# swt-001.net
KiCad netlist of a schematic drawn in EAGLE
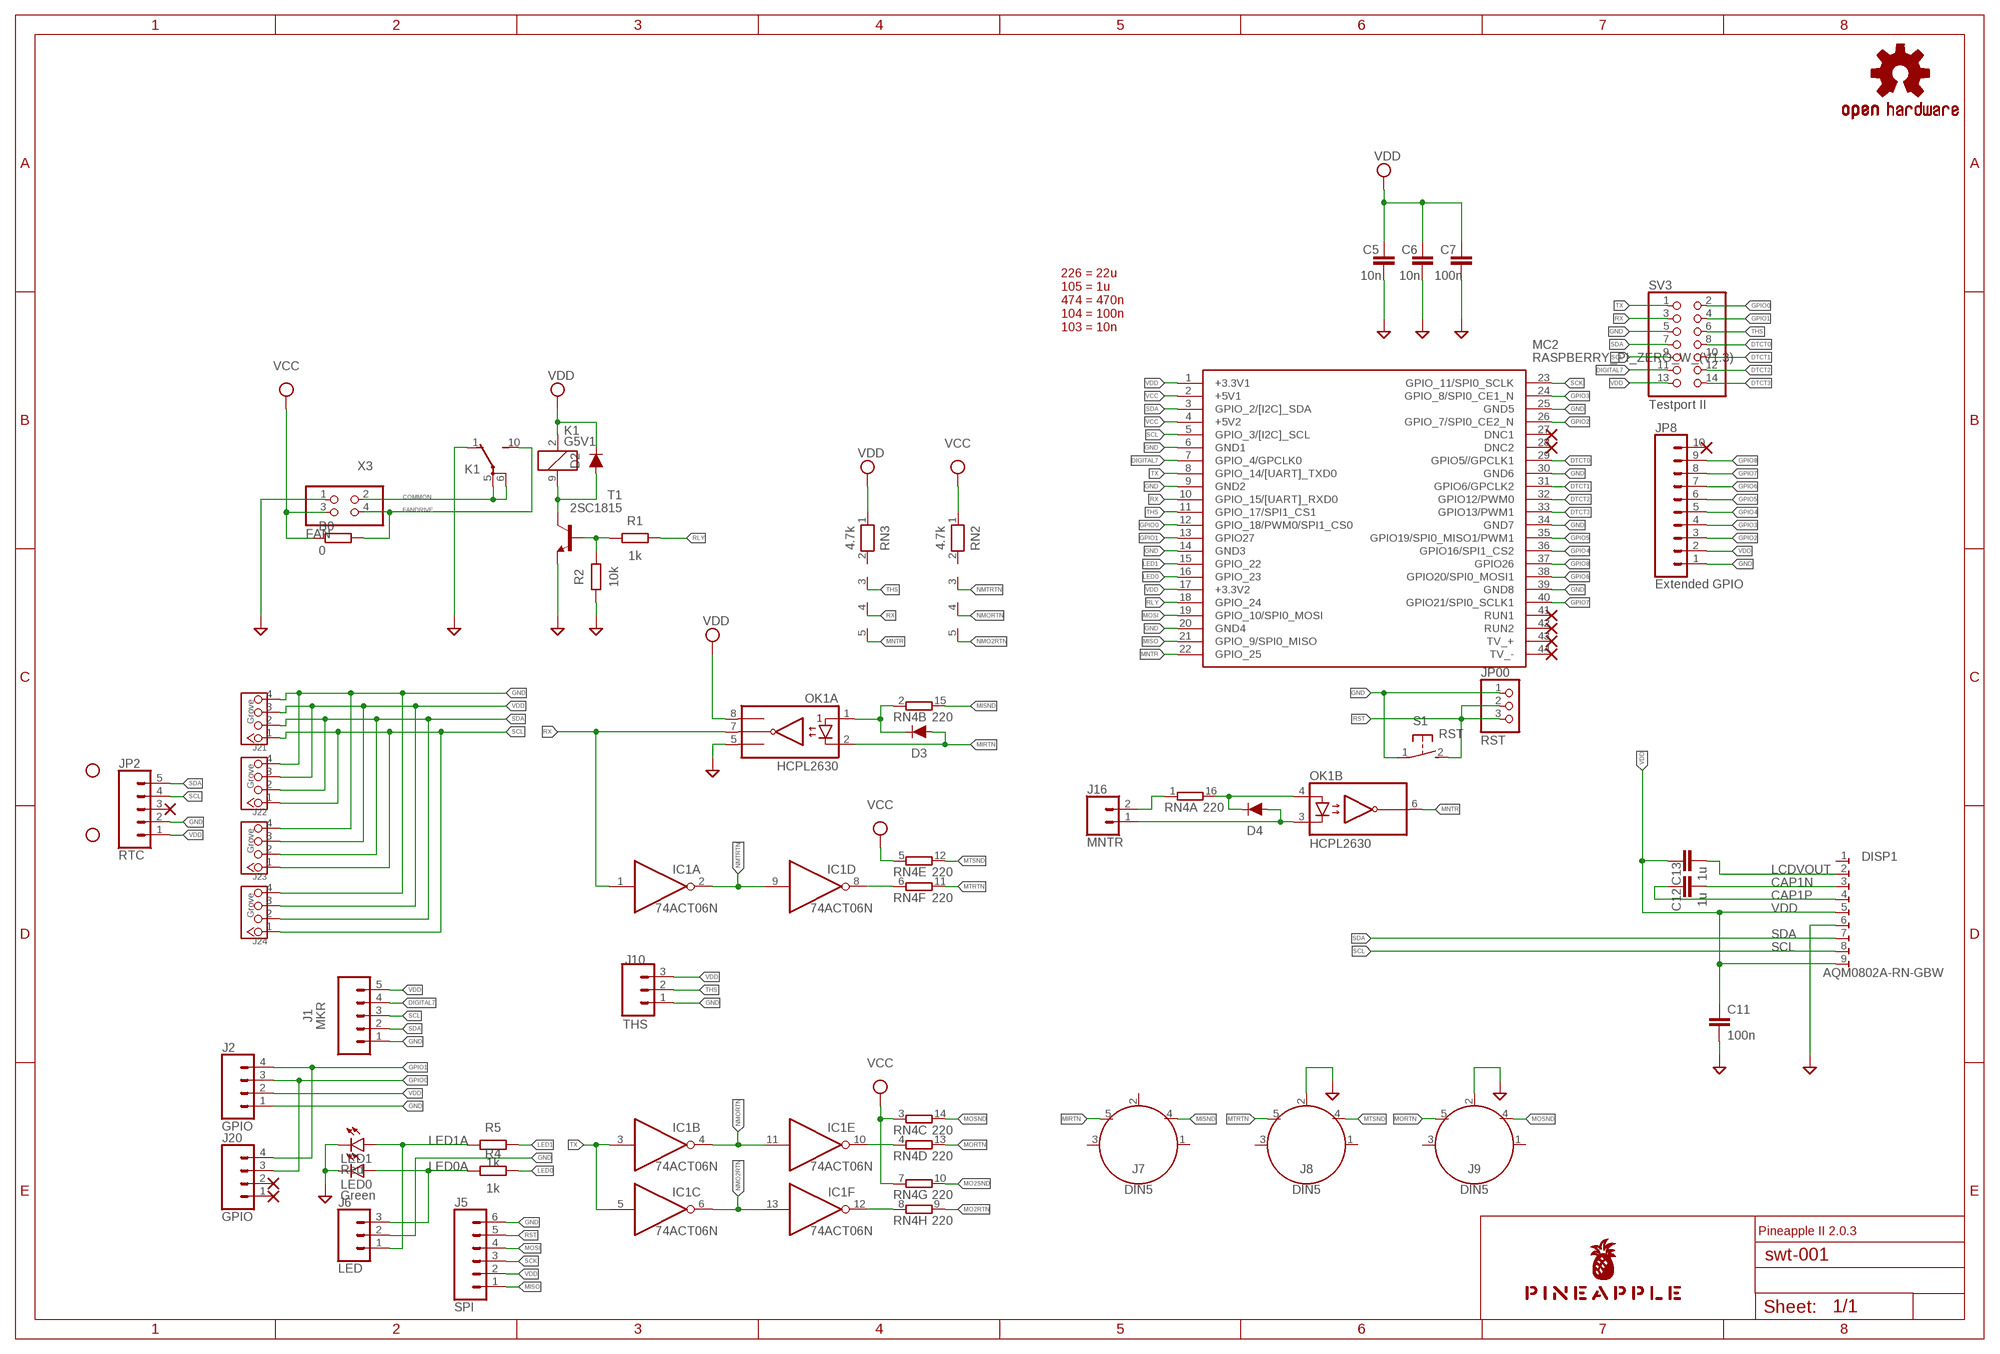
[diagram p0: schematic, sheet 1]

(export (version "E")
  (design (tool "Eeschema 10.0.6"))
  (components
    (comp (ref "B0")
      (value "0")
      (footprint "eagle-import:M3216")
      (libsource (lib "eagle-import") (part "R-EU_M3216"))
    )
    (comp (ref "C5")
      (value "10n")
      (footprint "eagle-import:C025-024X044")
      (libsource (lib "eagle-import") (part "resistor_348_C-EU025-024X044"))
    )
    (comp (ref "C6")
      (value "10n")
      (footprint "eagle-import:C025-024X044")
      (libsource (lib "eagle-import") (part "resistor_348_C-EU025-024X044"))
    )
    (comp (ref "C7")
      (value "100n")
      (footprint "eagle-import:C025-024X044")
      (libsource (lib "eagle-import") (part "resistor_348_C-EU025-024X044"))
    )
    (comp (ref "C11")
      (value "100n")
      (footprint "eagle-import:C025-024X044")
      (libsource (lib "eagle-import") (part "C-EU025-024X044"))
    )
    (comp (ref "C12")
      (value "1u")
      (footprint "eagle-import:C050-024X044")
      (libsource (lib "eagle-import") (part "C-EU050-024X044"))
    )
    (comp (ref "C13")
      (value "1u")
      (footprint "eagle-import:C050-024X044")
      (libsource (lib "eagle-import") (part "C-EU050-024X044"))
    )
    (comp (ref "D2")
      (value "DIODE-1N4148")
      (footprint "eagle-import:DIODE-1N4148")
      (libsource (lib "eagle-import") (part "DIODE-1N4148"))
    )
    (comp (ref "D3")
      (value "DIODE-1N4148")
      (footprint "eagle-import:DIODE-1N4148")
      (libsource (lib "eagle-import") (part "DIODE-1N4148"))
    )
    (comp (ref "D4")
      (value "DIODE-1N4148")
      (footprint "eagle-import:DIODE-1N4148")
      (libsource (lib "eagle-import") (part "DIODE-1N4148"))
    )
    (comp (ref "DISP1")
      (value "AQM0802A-RN-GBW")
      (footprint "eagle-import:AQM0802A-RN-GBW-FOOTPRINT")
      (libsource (lib "eagle-import") (part "AQM0802A-RN-GBW"))
    )
    (comp (ref "H1")
      (value "STAND-OFF")
      (footprint "eagle-import:STAND-OFF")
      (libsource (lib "eagle-import") (part "STAND-OFF"))
    )
    (comp (ref "H2")
      (value "STAND-OFF")
      (footprint "eagle-import:STAND-OFF")
      (libsource (lib "eagle-import") (part "STAND-OFF"))
    )
    (comp (ref "IC1")
      (value "74ACT06N")
      (footprint "eagle-import:DIL14")
      (libsource (lib "eagle-import") (part "7406NACT"))
    )
    (comp (ref "J1")
      (value "MKR")
      (footprint "eagle-import:JST-5-PTH")
      (libsource (lib "eagle-import") (part "CONN_05JST"))
    )
    (comp (ref "J2")
      (value "GPIO")
      (footprint "eagle-import:JST-4-PTH")
      (libsource (lib "eagle-import") (part "CONN_04JST-PTH"))
    )
    (comp (ref "J5")
      (value "SPI")
      (footprint "eagle-import:1X06_1.27MM")
      (libsource (lib "eagle-import") (part "CONN_061.27MM"))
    )
    (comp (ref "J6")
      (value "LED")
      (footprint "eagle-import:JST-3-PTH-VERT")
      (libsource (lib "eagle-import") (part "CONN_03JST-PTH-VERT"))
    )
    (comp (ref "J7")
      (value "DIN5")
      (footprint "eagle-import:DIN5-RA-PTH")
      (libsource (lib "eagle-import") (part "DIN5"))
    )
    (comp (ref "J8")
      (value "DIN5")
      (footprint "eagle-import:DIN5-RA-PTH")
      (libsource (lib "eagle-import") (part "DIN5"))
    )
    (comp (ref "J9")
      (value "DIN5")
      (footprint "eagle-import:DIN5-RA-PTH")
      (libsource (lib "eagle-import") (part "DIN5"))
    )
    (comp (ref "J10")
      (value "THS")
      (footprint "eagle-import:JST-3-PTH-VERT")
      (libsource (lib "eagle-import") (part "CONN_03JST-PTH-VERT"))
    )
    (comp (ref "J16")
      (value "MNTR")
      (footprint "eagle-import:JST-2-PTH-NS")
      (libsource (lib "eagle-import") (part "CONN_02-JST-2-PTH-NO_SILK"))
    )
    (comp (ref "J20")
      (value "GPIO")
      (footprint "eagle-import:1X04_1.27MM")
      (libsource (lib "eagle-import") (part "CONN_041.27MM"))
    )
    (comp (ref "J21")
      (value "Grove")
      (footprint "eagle-import:4P-2.0-90D")
      (libsource (lib "eagle-import") (part "TWIG-4P-2.0'90D'"))
    )
    (comp (ref "J22")
      (value "Grove")
      (footprint "eagle-import:4P-2.0-90D")
      (libsource (lib "eagle-import") (part "TWIG-4P-2.0'90D'"))
    )
    (comp (ref "J23")
      (value "Grove")
      (footprint "eagle-import:4P-2.0-W_O-BUCKLE")
      (libsource (lib "eagle-import") (part "TWIG-4P-2.0"))
    )
    (comp (ref "J24")
      (value "Grove")
      (footprint "eagle-import:4P-2.0-W_O-BUCKLE")
      (libsource (lib "eagle-import") (part "TWIG-4P-2.0"))
    )
    (comp (ref "JP00")
      (value "RST")
      (footprint "eagle-import:1X03")
      (libsource (lib "eagle-import") (part "PINHD-1X3"))
    )
    (comp (ref "JP2")
      (value "RTC")
      (footprint "eagle-import:1X05")
      (libsource (lib "eagle-import") (part "CONN_05PTH"))
    )
    (comp (ref "JP8")
      (value "Extended GPIO")
      (footprint "eagle-import:1X10_LOCK")
      (libsource (lib "eagle-import") (part "CONN_10LOCK"))
    )
    (comp (ref "K1")
      (value "G5V1")
      (footprint "eagle-import:G5V1")
      (fields (field (name "MPN") "G5V-1-DC24"))
      (libsource (lib "eagle-import") (part "G5V1"))
    )
    (comp (ref "LED0")
      (value "Green")
      (footprint "eagle-import:CHIPLED_0603")
      (libsource (lib "eagle-import") (part "LEDCHIPLED_0603"))
    )
    (comp (ref "LED1")
      (value "Red")
      (footprint "eagle-import:CHIPLED_0603")
      (libsource (lib "eagle-import") (part "LEDCHIPLED_0603"))
    )
    (comp (ref "LOGO1")
      (value "OSHW-LOGOS-COPPER")
      (footprint "eagle-import:OSHW-LOGO-S_COPPER")
      (libsource (lib "eagle-import") (part "OSHW-LOGOS-COPPER"))
    )
    (comp (ref "MC2")
      (value "RASPBERRY_PI_ZERO_W_(V1.3)")
      (footprint "eagle-import:RASPBERRYPIZEROWV13")
      (fields (field (name "ARROW_PART_NUMBER") "Raspberry Pi Zero W (v1.3)"))
      (libsource (lib "eagle-import") (part "RASPBERRY_PI_ZERO_W_(V1.3)"))
    )
    (comp (ref "OK1")
      (value "HCPL2630")
      (footprint "eagle-import:DIL08")
      (fields (field (name "MF") "AGILENT TECHNOLOGIES") (field (name "MPN") "HCPL-2630-000E"))
      (libsource (lib "eagle-import") (part "HCPL2630"))
    )
    (comp (ref "R1")
      (value "1k")
      (footprint "eagle-import:0204_5")
      (libsource (lib "eagle-import") (part "resistor_348_R-EU_0204/5"))
    )
    (comp (ref "R2")
      (value "10k")
      (footprint "eagle-import:0204_5")
      (libsource (lib "eagle-import") (part "resistor_348_R-EU_0204/5"))
    )
    (comp (ref "R4")
      (value "1k")
      (footprint "eagle-import:0204_5")
      (libsource (lib "eagle-import") (part "resistor_348_R-EU_0204/5"))
    )
    (comp (ref "R5")
      (value "1k")
      (footprint "eagle-import:0204_5")
      (libsource (lib "eagle-import") (part "resistor_348_R-EU_0204/5"))
    )
    (comp (ref "RN2")
      (value "4.7k")
      (footprint "eagle-import:RN-5")
      (libsource (lib "eagle-import") (part "RN04"))
    )
    (comp (ref "RN3")
      (value "4.7k")
      (footprint "eagle-import:RN-5")
      (libsource (lib "eagle-import") (part "RN04"))
    )
    (comp (ref "RN4")
      (value "220")
      (footprint "eagle-import:DIL16")
      (libsource (lib "eagle-import") (part "8R-N"))
    )
    (comp (ref "S1")
      (value "RST")
      (footprint "eagle-import:B3F-31XX")
      (fields (field (name "MPN") "B3F-3100"))
      (libsource (lib "eagle-import") (part "31-XX"))
    )
    (comp (ref "SV3")
      (value "Testport II")
      (footprint "eagle-import:2X07")
      (libsource (lib "eagle-import") (part "PINHD-2X7"))
    )
    (comp (ref "T1")
      (value "2SC1815")
      (footprint "eagle-import:TO92-ECB")
      (libsource (lib "eagle-import") (part "2SC1815"))
    )
    (comp (ref "U$1")
      (value "PINEAPPLE450_SILK")
      (footprint "eagle-import:PINEAPPLE450_SILK")
      (libsource (lib "eagle-import") (part "PINEAPPLE450_SILK"))
    )
    (comp (ref "X3")
      (value "FAN")
      (footprint "eagle-import:2X02")
      (libsource (lib "eagle-import") (part "PINHD-2X2"))
    )
  )
  (nets
    (net (code "1") (name "/CAP1N") (class "Default")
      (node (ref "C12") (pin "2") (pinfunction "2_2") (pintype "passive"))
      (node (ref "DISP1") (pin "3") (pinfunction "3_3") (pintype "passive"))
    )
    (net (code "2") (name "/CAP1P") (class "Default")
      (node (ref "C12") (pin "1") (pinfunction "1_1") (pintype "passive"))
      (node (ref "DISP1") (pin "4") (pinfunction "4_4") (pintype "passive"))
    )
    (net (code "3") (name "/COMMON") (class "Default")
      (node (ref "K1") (pin "5") (pinfunction "P_5") (pintype "passive"))
      (node (ref "K1") (pin "6") (pinfunction "P_6") (pintype "passive"))
      (node (ref "X3") (pin "2") (pinfunction "2_2") (pintype "passive"))
    )
    (net (code "4") (name "/FANDRIVE") (class "Default")
      (node (ref "B0") (pin "2") (pinfunction "2_2") (pintype "passive"))
      (node (ref "K1") (pin "10") (pinfunction "S_10") (pintype "passive"))
      (node (ref "X3") (pin "4") (pinfunction "4_4") (pintype "passive"))
    )
    (net (code "5") (name "/LCDVOUT") (class "Default")
      (node (ref "C13") (pin "2") (pinfunction "2_2") (pintype "passive"))
      (node (ref "DISP1") (pin "2") (pinfunction "2_2") (pintype "passive"))
    )
    (net (code "6") (name "/LED0A") (class "Default")
      (node (ref "J6") (pin "3") (pinfunction "3_3") (pintype "passive"))
      (node (ref "LED0") (pin "A") (pinfunction "A_A") (pintype "passive"))
      (node (ref "R4") (pin "1") (pinfunction "1_1") (pintype "passive"))
    )
    (net (code "7") (name "/LED1A") (class "Default")
      (node (ref "J6") (pin "1") (pinfunction "1_1") (pintype "passive"))
      (node (ref "LED1") (pin "A") (pinfunction "A_A") (pintype "passive"))
      (node (ref "R5") (pin "1") (pinfunction "1_1") (pintype "passive"))
    )
    (net (code "8") (name "DIGITAL7") (class "Default")
      (node (ref "J1") (pin "4") (pinfunction "4_4") (pintype "passive"))
      (node (ref "MC2") (pin "7") (pinfunction "GPIO_4/GPCLK0_7") (pintype "bidirectional"))
      (node (ref "SV3") (pin "11") (pinfunction "11_11") (pintype "passive"))
    )
    (net (code "9") (name "DTCT0") (class "Default")
      (node (ref "MC2") (pin "29") (pinfunction "GPIO5//GPCLK1_29") (pintype "bidirectional"))
      (node (ref "SV3") (pin "8") (pinfunction "8_8") (pintype "passive"))
    )
    (net (code "10") (name "DTCT1") (class "Default")
      (node (ref "MC2") (pin "31") (pinfunction "GPIO6/GPCLK2_31") (pintype "bidirectional"))
      (node (ref "SV3") (pin "10") (pinfunction "10_10") (pintype "passive"))
    )
    (net (code "11") (name "DTCT2") (class "Default")
      (node (ref "MC2") (pin "32") (pinfunction "GPIO12/PWM0_32") (pintype "bidirectional"))
      (node (ref "SV3") (pin "12") (pinfunction "12_12") (pintype "passive"))
    )
    (net (code "12") (name "DTCT3") (class "Default")
      (node (ref "MC2") (pin "33") (pinfunction "GPIO13/PWM1_33") (pintype "bidirectional"))
      (node (ref "SV3") (pin "14") (pinfunction "14_14") (pintype "passive"))
    )
    (net (code "13") (name "GND") (class "Default")
      (node (ref "C11") (pin "2") (pinfunction "2_2") (pintype "passive"))
      (node (ref "C5") (pin "2") (pinfunction "2_2") (pintype "passive"))
      (node (ref "C6") (pin "2") (pinfunction "2_2") (pintype "passive"))
      (node (ref "C7") (pin "2") (pinfunction "2_2") (pintype "passive"))
      (node (ref "DISP1") (pin "6") (pinfunction "6_6") (pintype "passive"))
      (node (ref "J1") (pin "1") (pinfunction "1_1") (pintype "passive"))
      (node (ref "J10") (pin "1") (pinfunction "1_1") (pintype "passive"))
      (node (ref "J2") (pin "1") (pinfunction "1_1") (pintype "passive"))
      (node (ref "J21") (pin "4") (pinfunction "4_4") (pintype "bidirectional"))
      (node (ref "J22") (pin "4") (pinfunction "4_4") (pintype "bidirectional"))
      (node (ref "J23") (pin "4") (pinfunction "4_4") (pintype "bidirectional"))
      (node (ref "J24") (pin "4") (pinfunction "4_4") (pintype "bidirectional"))
      (node (ref "J5") (pin "6") (pinfunction "6_6") (pintype "passive"))
      (node (ref "J6") (pin "2") (pinfunction "2_2") (pintype "passive"))
      (node (ref "J8") (pin "2") (pinfunction "2_2") (pintype "bidirectional"))
      (node (ref "J9") (pin "2") (pinfunction "2_2") (pintype "bidirectional"))
      (node (ref "JP00") (pin "1") (pinfunction "1_1") (pintype "passive"))
      (node (ref "JP2") (pin "2") (pinfunction "2_2") (pintype "passive"))
      (node (ref "JP8") (pin "1") (pinfunction "1_1") (pintype "passive"))
      (node (ref "K1") (pin "1") (pinfunction "O_1") (pintype "passive"))
      (node (ref "LED0") (pin "C") (pinfunction "C_C") (pintype "passive"))
      (node (ref "LED1") (pin "C") (pinfunction "C_C") (pintype "passive"))
      (node (ref "MC2") (pin "14") (pinfunction "GND3_14") (pintype "bidirectional"))
      (node (ref "MC2") (pin "20") (pinfunction "GND4_20") (pintype "bidirectional"))
      (node (ref "MC2") (pin "25") (pinfunction "GND5_25") (pintype "bidirectional"))
      (node (ref "MC2") (pin "30") (pinfunction "GND6_30") (pintype "bidirectional"))
      (node (ref "MC2") (pin "34") (pinfunction "GND7_34") (pintype "bidirectional"))
      (node (ref "MC2") (pin "39") (pinfunction "GND8_39") (pintype "bidirectional"))
      (node (ref "MC2") (pin "6") (pinfunction "GND1_6") (pintype "bidirectional"))
      (node (ref "MC2") (pin "9") (pinfunction "GND2_9") (pintype "bidirectional"))
      (node (ref "OK1") (pin "5") (pinfunction "GND_5") (pintype "passive"))
      (node (ref "R2") (pin "1") (pinfunction "1_1") (pintype "passive"))
      (node (ref "S1") (pin "1") (pinfunction "P_1") (pintype "passive"))
      (node (ref "SV3") (pin "5") (pinfunction "5_5") (pintype "passive"))
      (node (ref "T1") (pin "E") (pinfunction "E_E") (pintype "passive"))
      (node (ref "X3") (pin "1") (pinfunction "1_1") (pintype "passive"))
    )
    (net (code "14") (name "GPIO0") (class "Default")
      (node (ref "J2") (pin "3") (pinfunction "3_3") (pintype "passive"))
      (node (ref "J20") (pin "3") (pinfunction "3_3") (pintype "passive"))
      (node (ref "MC2") (pin "12") (pinfunction "GPIO_18/PWM0/SPI1_CS0_12") (pintype "bidirectional"))
      (node (ref "SV3") (pin "2") (pinfunction "2_2") (pintype "passive"))
    )
    (net (code "15") (name "GPIO1") (class "Default")
      (node (ref "J2") (pin "4") (pinfunction "4_4") (pintype "passive"))
      (node (ref "J20") (pin "4") (pinfunction "4_4") (pintype "passive"))
      (node (ref "MC2") (pin "13") (pinfunction "GPIO27_13") (pintype "bidirectional"))
      (node (ref "SV3") (pin "4") (pinfunction "4_4") (pintype "passive"))
    )
    (net (code "16") (name "GPIO2") (class "Default")
      (node (ref "JP8") (pin "3") (pinfunction "3_3") (pintype "passive"))
      (node (ref "MC2") (pin "26") (pinfunction "GPIO_7/SPI0_CE2_N_26") (pintype "bidirectional"))
    )
    (net (code "17") (name "GPIO3") (class "Default")
      (node (ref "JP8") (pin "4") (pinfunction "4_4") (pintype "passive"))
      (node (ref "MC2") (pin "24") (pinfunction "GPIO_8/SPI0_CE1_N_24") (pintype "bidirectional"))
    )
    (net (code "18") (name "GPIO4") (class "Default")
      (node (ref "JP8") (pin "5") (pinfunction "5_5") (pintype "passive"))
      (node (ref "MC2") (pin "36") (pinfunction "GPIO16/SPI1_CS2_36") (pintype "bidirectional"))
    )
    (net (code "19") (name "GPIO5") (class "Default")
      (node (ref "JP8") (pin "6") (pinfunction "6_6") (pintype "passive"))
      (node (ref "MC2") (pin "35") (pinfunction "GPIO19/SPI0_MISO1/PWM1_35") (pintype "bidirectional"))
    )
    (net (code "20") (name "GPIO6") (class "Default")
      (node (ref "JP8") (pin "7") (pinfunction "7_7") (pintype "passive"))
      (node (ref "MC2") (pin "38") (pinfunction "GPIO20/SPI0_MOSI1_38") (pintype "bidirectional"))
    )
    (net (code "21") (name "GPIO7") (class "Default")
      (node (ref "JP8") (pin "8") (pinfunction "8_8") (pintype "passive"))
      (node (ref "MC2") (pin "40") (pinfunction "GPIO21/SPI0_SCLK1_40") (pintype "bidirectional"))
    )
    (net (code "22") (name "GPIO8") (class "Default")
      (node (ref "JP8") (pin "9") (pinfunction "9_9") (pintype "passive"))
      (node (ref "MC2") (pin "37") (pinfunction "GPIO26_37") (pintype "bidirectional"))
    )
    (net (code "23") (name "LED0") (class "Default")
      (node (ref "MC2") (pin "16") (pinfunction "GPIO_23_16") (pintype "bidirectional"))
      (node (ref "R4") (pin "2") (pinfunction "2_2") (pintype "passive"))
    )
    (net (code "24") (name "LED1") (class "Default")
      (node (ref "MC2") (pin "15") (pinfunction "GPIO_22_15") (pintype "bidirectional"))
      (node (ref "R5") (pin "2") (pinfunction "2_2") (pintype "passive"))
    )
    (net (code "25") (name "MIRTN") (class "Default")
      (node (ref "D3") (pin "A") (pinfunction "A_A") (pintype "passive"))
      (node (ref "J7") (pin "5") (pinfunction "5_5") (pintype "bidirectional"))
      (node (ref "OK1") (pin "2") (pinfunction "C1_2") (pintype "passive"))
    )
    (net (code "26") (name "MISND") (class "Default")
      (node (ref "J7") (pin "4") (pinfunction "4_4") (pintype "bidirectional"))
      (node (ref "RN4") (pin "15") (pinfunction "2_15") (pintype "passive"))
    )
    (net (code "27") (name "MISO") (class "Default")
      (node (ref "J5") (pin "1") (pinfunction "1_1") (pintype "passive"))
      (node (ref "MC2") (pin "21") (pinfunction "GPIO_9/SPI0_MISO_21") (pintype "bidirectional"))
    )
    (net (code "28") (name "MNTR") (class "Default")
      (node (ref "MC2") (pin "22") (pinfunction "GPIO_25_22") (pintype "bidirectional"))
      (node (ref "OK1") (pin "6") (pinfunction "VO2_6") (pintype "passive"))
      (node (ref "RN3") (pin "5") (pinfunction "5_5") (pintype "passive"))
    )
    (net (code "29") (name "MO2RTN") (class "Default")
      (node (ref "RN4") (pin "9") (pinfunction "2_9") (pintype "passive"))
    )
    (net (code "30") (name "MO2SND") (class "Default")
      (node (ref "RN4") (pin "10") (pinfunction "2_10") (pintype "passive"))
    )
    (net (code "31") (name "MORTN") (class "Default")
      (node (ref "J9") (pin "5") (pinfunction "5_5") (pintype "bidirectional"))
      (node (ref "RN4") (pin "13") (pinfunction "2_13") (pintype "passive"))
    )
    (net (code "32") (name "MOSI") (class "Default")
      (node (ref "J5") (pin "4") (pinfunction "4_4") (pintype "passive"))
      (node (ref "MC2") (pin "19") (pinfunction "GPIO_10/SPI0_MOSI_19") (pintype "bidirectional"))
    )
    (net (code "33") (name "MOSND") (class "Default")
      (node (ref "J9") (pin "4") (pinfunction "4_4") (pintype "bidirectional"))
      (node (ref "RN4") (pin "14") (pinfunction "2_14") (pintype "passive"))
    )
    (net (code "34") (name "MTRTN") (class "Default")
      (node (ref "J8") (pin "5") (pinfunction "5_5") (pintype "bidirectional"))
      (node (ref "RN4") (pin "11") (pinfunction "2_11") (pintype "passive"))
    )
    (net (code "35") (name "MTSND") (class "Default")
      (node (ref "J8") (pin "4") (pinfunction "4_4") (pintype "bidirectional"))
      (node (ref "RN4") (pin "12") (pinfunction "2_12") (pintype "passive"))
    )
    (net (code "36") (name "NMO2RTN") (class "Default")
      (node (ref "IC1") (pin "13") (pinfunction "I_13") (pintype "input"))
      (node (ref "IC1") (pin "6") (pinfunction "O_6") (pintype "open_collector"))
      (node (ref "RN2") (pin "5") (pinfunction "5_5") (pintype "passive"))
    )
    (net (code "37") (name "NMORTN") (class "Default")
      (node (ref "IC1") (pin "11") (pinfunction "I_11") (pintype "input"))
      (node (ref "IC1") (pin "4") (pinfunction "O_4") (pintype "open_collector"))
      (node (ref "RN2") (pin "4") (pinfunction "4_4") (pintype "passive"))
    )
    (net (code "38") (name "NMTRTN") (class "Default")
      (node (ref "IC1") (pin "2") (pinfunction "O_2") (pintype "open_collector"))
      (node (ref "IC1") (pin "9") (pinfunction "I_9") (pintype "input"))
      (node (ref "RN2") (pin "3") (pinfunction "3_3") (pintype "passive"))
    )
    (net (code "39") (name "Net-(IC1D-O)") (class "Default")
      (node (ref "IC1") (pin "8") (pinfunction "O_8") (pintype "open_collector"))
      (node (ref "RN4") (pin "6") (pinfunction "1_6") (pintype "passive"))
    )
    (net (code "40") (name "Net-(IC1E-O)") (class "Default")
      (node (ref "IC1") (pin "10") (pinfunction "O_10") (pintype "open_collector"))
      (node (ref "RN4") (pin "4") (pinfunction "1_4") (pintype "passive"))
    )
    (net (code "41") (name "Net-(IC1F-O)") (class "Default")
      (node (ref "IC1") (pin "12") (pinfunction "O_12") (pintype "open_collector"))
      (node (ref "RN4") (pin "8") (pinfunction "1_8") (pintype "passive"))
    )
    (net (code "42") (name "Net-(J16-Pad2)") (class "Default")
      (node (ref "J16") (pin "2") (pinfunction "2_2") (pintype "passive"))
      (node (ref "RN4") (pin "1") (pinfunction "1_1") (pintype "passive"))
    )
    (net (code "43") (name "Net-(K1A-2)") (class "Default")
      (node (ref "D2") (pin "A") (pinfunction "A_A") (pintype "passive"))
      (node (ref "K1") (pin "9") (pinfunction "2_9") (pintype "passive"))
      (node (ref "T1") (pin "C") (pinfunction "C_C") (pintype "passive"))
    )
    (net (code "44") (name "Net-(OK1A-A1)") (class "Default")
      (node (ref "D3") (pin "C") (pinfunction "C_C") (pintype "passive"))
      (node (ref "OK1") (pin "1") (pinfunction "A1_1") (pintype "passive"))
      (node (ref "RN4") (pin "2") (pinfunction "1_2") (pintype "passive"))
    )
    (net (code "45") (name "Net-(OK1B-A2)") (class "Default")
      (node (ref "D4") (pin "C") (pinfunction "C_C") (pintype "passive"))
      (node (ref "OK1") (pin "4") (pinfunction "A2_4") (pintype "passive"))
      (node (ref "RN4") (pin "16") (pinfunction "2_16") (pintype "passive"))
    )
    (net (code "46") (name "Net-(OK1B-C2)") (class "Default")
      (node (ref "D4") (pin "A") (pinfunction "A_A") (pintype "passive"))
      (node (ref "J16") (pin "1") (pinfunction "1_1") (pintype "passive"))
      (node (ref "OK1") (pin "3") (pinfunction "C2_3") (pintype "passive"))
    )
    (net (code "47") (name "Net-(R1-Pad1)") (class "Default")
      (node (ref "R1") (pin "1") (pinfunction "1_1") (pintype "passive"))
      (node (ref "R2") (pin "2") (pinfunction "2_2") (pintype "passive"))
      (node (ref "T1") (pin "B") (pinfunction "B_B") (pintype "passive"))
    )
    (net (code "48") (name "RLY") (class "Default")
      (node (ref "MC2") (pin "18") (pinfunction "GPIO_24_18") (pintype "bidirectional"))
      (node (ref "R1") (pin "2") (pinfunction "2_2") (pintype "passive"))
    )
    (net (code "49") (name "RST") (class "Default")
      (node (ref "J5") (pin "5") (pinfunction "5_5") (pintype "passive"))
      (node (ref "JP00") (pin "2") (pinfunction "2_2") (pintype "passive"))
      (node (ref "JP00") (pin "3") (pinfunction "3_3") (pintype "passive"))
      (node (ref "S1") (pin "2") (pinfunction "S_2") (pintype "passive"))
    )
    (net (code "50") (name "RX") (class "Default")
      (node (ref "IC1") (pin "1") (pinfunction "I_1") (pintype "input"))
      (node (ref "MC2") (pin "10") (pinfunction "GPIO_15/[UART]_RXD0_10") (pintype "bidirectional"))
      (node (ref "OK1") (pin "7") (pinfunction "VO1_7") (pintype "passive"))
      (node (ref "RN3") (pin "4") (pinfunction "4_4") (pintype "passive"))
      (node (ref "SV3") (pin "3") (pinfunction "3_3") (pintype "passive"))
    )
    (net (code "51") (name "SCK") (class "Default")
      (node (ref "J5") (pin "3") (pinfunction "3_3") (pintype "passive"))
      (node (ref "MC2") (pin "23") (pinfunction "GPIO_11/SPI0_SCLK_23") (pintype "bidirectional"))
    )
    (net (code "52") (name "SCL") (class "Default")
      (node (ref "DISP1") (pin "8") (pinfunction "8_8") (pintype "passive"))
      (node (ref "J1") (pin "3") (pinfunction "3_3") (pintype "passive"))
      (node (ref "J21") (pin "1") (pinfunction "1_1") (pintype "bidirectional"))
      (node (ref "J22") (pin "1") (pinfunction "1_1") (pintype "bidirectional"))
      (node (ref "J23") (pin "1") (pinfunction "1_1") (pintype "bidirectional"))
      (node (ref "J24") (pin "1") (pinfunction "1_1") (pintype "bidirectional"))
      (node (ref "JP2") (pin "4") (pinfunction "4_4") (pintype "passive"))
      (node (ref "MC2") (pin "5") (pinfunction "GPIO_3/[I2C]_SCL_5") (pintype "bidirectional"))
      (node (ref "SV3") (pin "9") (pinfunction "9_9") (pintype "passive"))
    )
    (net (code "53") (name "SDA") (class "Default")
      (node (ref "DISP1") (pin "7") (pinfunction "7_7") (pintype "passive"))
      (node (ref "J1") (pin "2") (pinfunction "2_2") (pintype "passive"))
      (node (ref "J21") (pin "2") (pinfunction "2_2") (pintype "bidirectional"))
      (node (ref "J22") (pin "2") (pinfunction "2_2") (pintype "bidirectional"))
      (node (ref "J23") (pin "2") (pinfunction "2_2") (pintype "bidirectional"))
      (node (ref "J24") (pin "2") (pinfunction "2_2") (pintype "bidirectional"))
      (node (ref "JP2") (pin "5") (pinfunction "5_5") (pintype "passive"))
      (node (ref "MC2") (pin "3") (pinfunction "GPIO_2/[I2C]_SDA_3") (pintype "bidirectional"))
      (node (ref "SV3") (pin "7") (pinfunction "7_7") (pintype "passive"))
    )
    (net (code "54") (name "THS") (class "Default")
      (node (ref "J10") (pin "2") (pinfunction "2_2") (pintype "passive"))
      (node (ref "MC2") (pin "11") (pinfunction "GPIO_17/SPI1_CS1_11") (pintype "bidirectional"))
      (node (ref "RN3") (pin "3") (pinfunction "3_3") (pintype "passive"))
      (node (ref "SV3") (pin "6") (pinfunction "6_6") (pintype "passive"))
    )
    (net (code "55") (name "TX") (class "Default")
      (node (ref "IC1") (pin "3") (pinfunction "I_3") (pintype "input"))
      (node (ref "IC1") (pin "5") (pinfunction "I_5") (pintype "input"))
      (node (ref "MC2") (pin "8") (pinfunction "GPIO_14/[UART]_TXD0_8") (pintype "bidirectional"))
      (node (ref "SV3") (pin "1") (pinfunction "1_1") (pintype "passive"))
    )
    (net (code "56") (name "VCC") (class "Default")
      (node (ref "B0") (pin "1") (pinfunction "1_1") (pintype "passive"))
      (node (ref "MC2") (pin "2") (pinfunction "+5V1_2") (pintype "bidirectional"))
      (node (ref "MC2") (pin "4") (pinfunction "+5V2_4") (pintype "bidirectional"))
      (node (ref "RN2") (pin "1") (pinfunction "1_1") (pintype "passive"))
      (node (ref "RN4") (pin "3") (pinfunction "1_3") (pintype "passive"))
      (node (ref "RN4") (pin "5") (pinfunction "1_5") (pintype "passive"))
      (node (ref "RN4") (pin "7") (pinfunction "1_7") (pintype "passive"))
      (node (ref "X3") (pin "3") (pinfunction "3_3") (pintype "passive"))
    )
    (net (code "57") (name "VDD") (class "Default")
      (node (ref "C11") (pin "1") (pinfunction "1_1") (pintype "passive"))
      (node (ref "C13") (pin "1") (pinfunction "1_1") (pintype "passive"))
      (node (ref "C5") (pin "1") (pinfunction "1_1") (pintype "passive"))
      (node (ref "C6") (pin "1") (pinfunction "1_1") (pintype "passive"))
      (node (ref "C7") (pin "1") (pinfunction "1_1") (pintype "passive"))
      (node (ref "D2") (pin "C") (pinfunction "C_C") (pintype "passive"))
      (node (ref "DISP1") (pin "5") (pinfunction "5_5") (pintype "passive"))
      (node (ref "DISP1") (pin "9") (pinfunction "9_9") (pintype "passive"))
      (node (ref "J1") (pin "5") (pinfunction "5_5") (pintype "passive"))
      (node (ref "J10") (pin "3") (pinfunction "3_3") (pintype "passive"))
      (node (ref "J2") (pin "2") (pinfunction "2_2") (pintype "passive"))
      (node (ref "J21") (pin "3") (pinfunction "3_3") (pintype "bidirectional"))
      (node (ref "J22") (pin "3") (pinfunction "3_3") (pintype "bidirectional"))
      (node (ref "J23") (pin "3") (pinfunction "3_3") (pintype "bidirectional"))
      (node (ref "J24") (pin "3") (pinfunction "3_3") (pintype "bidirectional"))
      (node (ref "J5") (pin "2") (pinfunction "2_2") (pintype "passive"))
      (node (ref "JP2") (pin "1") (pinfunction "1_1") (pintype "passive"))
      (node (ref "JP8") (pin "2") (pinfunction "2_2") (pintype "passive"))
      (node (ref "K1") (pin "2") (pinfunction "1_2") (pintype "passive"))
      (node (ref "MC2") (pin "1") (pinfunction "+3.3V1_1") (pintype "bidirectional"))
      (node (ref "MC2") (pin "17") (pinfunction "+3.3V2_17") (pintype "bidirectional"))
      (node (ref "OK1") (pin "8") (pinfunction "VCC_8") (pintype "passive"))
      (node (ref "RN3") (pin "1") (pinfunction "1_1") (pintype "passive"))
      (node (ref "SV3") (pin "13") (pinfunction "13_13") (pintype "passive"))
    )
    (net (code "58") (name "unconnected-(DISP1-Pad1)") (class "Default")
      (node (ref "DISP1") (pin "1") (pinfunction "1_1") (pintype "passive"))
    )
    (net (code "59") (name "unconnected-(J7-Pad1)") (class "Default")
      (node (ref "J7") (pin "1") (pinfunction "1_1") (pintype "bidirectional"))
    )
    (net (code "60") (name "unconnected-(J7-Pad2)") (class "Default")
      (node (ref "J7") (pin "2") (pinfunction "2_2") (pintype "bidirectional"))
    )
    (net (code "61") (name "unconnected-(J7-Pad3)") (class "Default")
      (node (ref "J7") (pin "3") (pinfunction "3_3") (pintype "bidirectional"))
    )
    (net (code "62") (name "unconnected-(J8-Pad1)") (class "Default")
      (node (ref "J8") (pin "1") (pinfunction "1_1") (pintype "bidirectional"))
    )
    (net (code "63") (name "unconnected-(J8-Pad3)") (class "Default")
      (node (ref "J8") (pin "3") (pinfunction "3_3") (pintype "bidirectional"))
    )
    (net (code "64") (name "unconnected-(J9-Pad1)") (class "Default")
      (node (ref "J9") (pin "1") (pinfunction "1_1") (pintype "bidirectional"))
    )
    (net (code "65") (name "unconnected-(J9-Pad3)") (class "Default")
      (node (ref "J9") (pin "3") (pinfunction "3_3") (pintype "bidirectional"))
    )
    (net (code "66") (name "unconnected-(J20-Pad1)") (class "Default")
      (node (ref "J20") (pin "1") (pinfunction "1_1") (pintype "passive"))
    )
    (net (code "67") (name "unconnected-(J20-Pad2)") (class "Default")
      (node (ref "J20") (pin "2") (pinfunction "2_2") (pintype "passive"))
    )
    (net (code "68") (name "unconnected-(JP2-Pad3)") (class "Default")
      (node (ref "JP2") (pin "3") (pinfunction "3_3") (pintype "passive"))
    )
    (net (code "69") (name "unconnected-(JP8-Pad10)") (class "Default")
      (node (ref "JP8") (pin "10") (pinfunction "10_10") (pintype "passive"))
    )
    (net (code "70") (name "unconnected-(MC2-DNC1-Pad27)") (class "Default")
      (node (ref "MC2") (pin "27") (pinfunction "DNC1_27") (pintype "bidirectional"))
    )
    (net (code "71") (name "unconnected-(MC2-DNC2-Pad28)") (class "Default")
      (node (ref "MC2") (pin "28") (pinfunction "DNC2_28") (pintype "bidirectional"))
    )
    (net (code "72") (name "unconnected-(MC2-RUN1-Pad41)") (class "Default")
      (node (ref "MC2") (pin "41") (pinfunction "RUN1_41") (pintype "bidirectional"))
    )
    (net (code "73") (name "unconnected-(MC2-RUN2-Pad42)") (class "Default")
      (node (ref "MC2") (pin "42") (pinfunction "RUN2_42") (pintype "bidirectional"))
    )
    (net (code "74") (name "unconnected-(MC2-TV_+-Pad43)") (class "Default")
      (node (ref "MC2") (pin "43") (pinfunction "TV_+_43") (pintype "bidirectional"))
    )
    (net (code "75") (name "unconnected-(MC2-TV_--Pad44)") (class "Default")
      (node (ref "MC2") (pin "44") (pinfunction "TV_-_44") (pintype "bidirectional"))
    )
    (net (code "76") (name "unconnected-(RN2-Pad2)") (class "Default")
      (node (ref "RN2") (pin "2") (pinfunction "2_2") (pintype "passive"))
    )
    (net (code "77") (name "unconnected-(RN3-Pad2)") (class "Default")
      (node (ref "RN3") (pin "2") (pinfunction "2_2") (pintype "passive"))
    )
  )
)
